# TLV521.net
KiCad netlist of a schematic drawn in Altium Designer
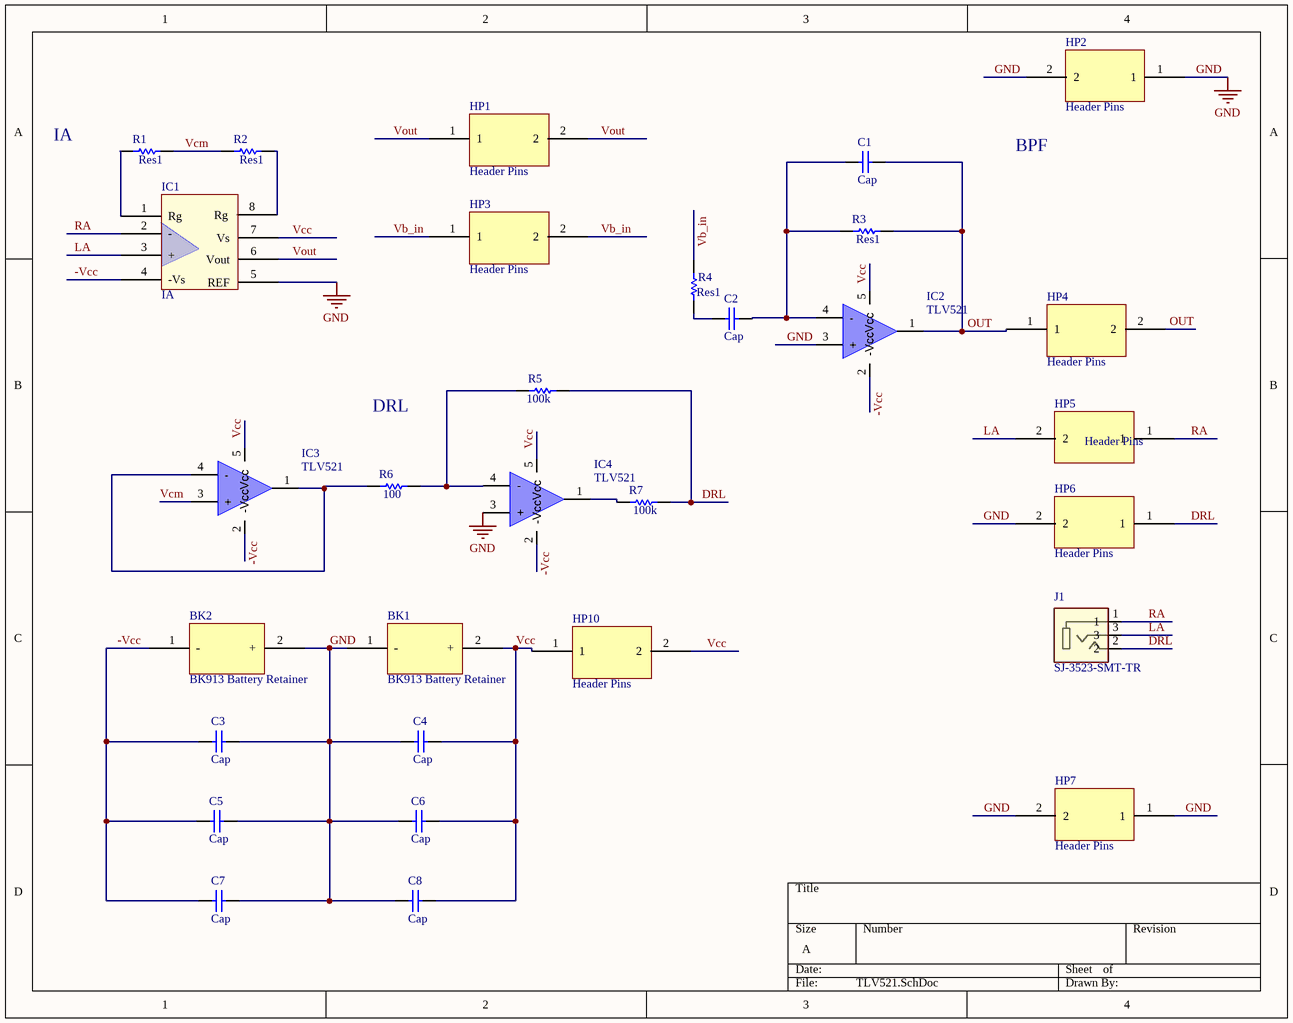
[diagram p0: TLV521.SchDoc]

(export (version "E")
  (design (tool "Eeschema 10.0.6"))
  (components
    (comp (ref "BK1")
      (value "BK913 Battery Retainer")
      (footprint "BK913")
      (description "BATTERY RETAINER COIN PC PIN")
      (libsource (lib "TLV521") (part "BK-913"))
    )
    (comp (ref "BK2")
      (value "BK913 Battery Retainer")
      (footprint "BK913")
      (description "BATTERY RETAINER COIN PC PIN")
      (libsource (lib "TLV521") (part "BK-913"))
    )
    (comp (ref "C1")
      (value "Cap")
      (footprint "6-0805_M")
      (description "Capacitor")
      (fields (field (name "PUBLISHER") "Altium Limited"))
      (libsource (lib "Miscellaneous Devices") (part "Cap"))
    )
    (comp (ref "C2")
      (value "Cap")
      (footprint "6-0805_M")
      (description "Capacitor")
      (fields (field (name "PUBLISHER") "Altium Limited"))
      (libsource (lib "Miscellaneous Devices") (part "Cap"))
    )
    (comp (ref "C3")
      (value "Cap")
      (footprint "6-0805_M")
      (description "Capacitor")
      (fields (field (name "PUBLISHER") "Altium Limited"))
      (libsource (lib "Miscellaneous Devices") (part "Cap"))
    )
    (comp (ref "C4")
      (value "Cap")
      (footprint "6-0805_M")
      (description "Capacitor")
      (fields (field (name "PUBLISHER") "Altium Limited"))
      (libsource (lib "Miscellaneous Devices") (part "Cap"))
    )
    (comp (ref "C5")
      (value "Cap")
      (footprint "6-0805_M")
      (description "Capacitor")
      (fields (field (name "PUBLISHER") "Altium Limited"))
      (libsource (lib "Miscellaneous Devices") (part "Cap"))
    )
    (comp (ref "C6")
      (value "Cap")
      (footprint "6-0805_M")
      (description "Capacitor")
      (fields (field (name "PUBLISHER") "Altium Limited"))
      (libsource (lib "Miscellaneous Devices") (part "Cap"))
    )
    (comp (ref "C7")
      (value "Cap")
      (footprint "6-0805_M")
      (description "Capacitor")
      (fields (field (name "PUBLISHER") "Altium Limited"))
      (libsource (lib "Miscellaneous Devices") (part "Cap"))
    )
    (comp (ref "C8")
      (value "Cap")
      (footprint "6-0805_M")
      (description "Capacitor")
      (fields (field (name "PUBLISHER") "Altium Limited"))
      (libsource (lib "Miscellaneous Devices") (part "Cap"))
    )
    (comp (ref "HP1")
      (value "Header Pins")
      (footprint "Header_Pins")
      (libsource (lib "") (part "Header Pins_1"))
    )
    (comp (ref "HP2")
      (value "Header Pins")
      (footprint "Header_Pins")
      (libsource (lib "TLV521") (part "Header Pins"))
    )
    (comp (ref "HP3")
      (value "Header Pins")
      (footprint "Header_Pins")
      (libsource (lib "") (part "Header Pins_1"))
    )
    (comp (ref "HP4")
      (value "Header Pins")
      (footprint "Header_Pins")
      (libsource (lib "") (part "Header Pins_1"))
    )
    (comp (ref "HP5")
      (value "Header Pins")
      (footprint "Header_Pins")
      (libsource (lib "TLV521") (part "Header Pins"))
    )
    (comp (ref "HP6")
      (value "Header Pins")
      (footprint "Header_Pins")
      (libsource (lib "TLV521") (part "Header Pins"))
    )
    (comp (ref "HP7")
      (value "Header Pins")
      (footprint "Header_Pins")
      (libsource (lib "TLV521") (part "Header Pins"))
    )
    (comp (ref "HP10")
      (value "Header Pins")
      (footprint "Header_Pins")
      (libsource (lib "") (part "Header Pins_1"))
    )
    (comp (ref "IC1")
      (value "IA")
      (footprint "SOP2")
      (description "IC OPAMP INSTR 1MHZ 8SOIC")
      (libsource (lib "TLV521") (part "AD620ARZ-REEL7"))
    )
    (comp (ref "IC2")
      (value "TLV521")
      (footprint "SOT65P210X110-5N")
      (description "IC OP AMP 6KHZ RR SC-70-5")
      (libsource (lib "TLV521") (part "TLV521DCKT"))
    )
    (comp (ref "IC3")
      (value "TLV521")
      (footprint "SOT65P210X110-5N")
      (description "IC OP AMP 6KHZ RR SC-70-5")
      (libsource (lib "TLV521") (part "TLV521DCKT"))
    )
    (comp (ref "IC4")
      (value "TLV521")
      (footprint "SOT65P210X110-5N")
      (description "IC OP AMP 6KHZ RR SC-70-5")
      (libsource (lib "TLV521") (part "TLV521DCKT"))
    )
    (comp (ref "J1")
      (value "SJ-3523-SMT-TR")
      (footprint "*CUI_SJ-3523-SMT-TR")
      (description "3.5 mm, Stereo, Right Angle, Surface Mount _SMT_, Audio Jack Connector")
      (fields (field (name "MF") "CUI Devices") (field (name "DIGI-KEY_PART_NUMBER") "CP-3523SJCT-ND"))
      (libsource (lib "TLV521") (part "SJ-3523-SMT-TR"))
    )
    (comp (ref "R1")
      (value "Res1")
      (footprint "6-0805_M")
      (description "Resistor")
      (fields (field (name "PUBLISHER") "Altium Limited"))
      (libsource (lib "Miscellaneous Devices") (part "Res1"))
    )
    (comp (ref "R2")
      (value "Res1")
      (footprint "6-0805_M")
      (description "Resistor")
      (fields (field (name "PUBLISHER") "Altium Limited"))
      (libsource (lib "Miscellaneous Devices") (part "Res1"))
    )
    (comp (ref "R3")
      (value "Res1")
      (footprint "6-0805_M")
      (description "Resistor")
      (fields (field (name "PUBLISHER") "Altium Limited"))
      (libsource (lib "Miscellaneous Devices") (part "Res1"))
    )
    (comp (ref "R4")
      (value "Res1")
      (footprint "6-0805_M")
      (description "Resistor")
      (fields (field (name "PUBLISHER") "Altium Limited"))
      (libsource (lib "Miscellaneous Devices") (part "Res1"))
    )
    (comp (ref "R5")
      (value "100k")
      (footprint "6-0805_M")
      (description "Resistor")
      (fields (field (name "PUBLISHER") "Altium Limited"))
      (libsource (lib "Miscellaneous Devices") (part "Res1"))
    )
    (comp (ref "R6")
      (value "100")
      (footprint "6-0805_M")
      (description "Resistor")
      (fields (field (name "PUBLISHER") "Altium Limited"))
      (libsource (lib "Miscellaneous Devices") (part "Res1"))
    )
    (comp (ref "R7")
      (value "100k")
      (footprint "6-0805_M")
      (description "Resistor")
      (fields (field (name "PUBLISHER") "Altium Limited"))
      (libsource (lib "Miscellaneous Devices") (part "Res1"))
    )
  )
  (nets
    (net (code "1") (name "/-Vcc") (class "Default")
      (node (ref "BK2") (pin "1") (pinfunction "-_1") (pintype "passive"))
      (node (ref "C3") (pin "1") (pinfunction "1_1") (pintype "passive"))
      (node (ref "C5") (pin "1") (pinfunction "1_1") (pintype "passive"))
      (node (ref "C7") (pin "1") (pinfunction "1_1") (pintype "passive"))
      (node (ref "IC1") (pin "4") (pinfunction "-Vs_4") (pintype "passive"))
      (node (ref "IC2") (pin "2") (pinfunction "-Vcc_2") (pintype "passive"))
      (node (ref "IC3") (pin "2") (pinfunction "-Vcc_2") (pintype "passive"))
      (node (ref "IC4") (pin "2") (pinfunction "-Vcc_2") (pintype "passive"))
    )
    (net (code "2") (name "/DRL") (class "Default")
      (node (ref "HP6") (pin "1") (pinfunction "1_1") (pintype "passive"))
      (node (ref "J1") (pin "2") (pinfunction "2_2") (pintype "passive"))
      (node (ref "R5") (pin "2") (pinfunction "2_2") (pintype "passive"))
      (node (ref "R7") (pin "2") (pinfunction "2_2") (pintype "passive"))
    )
    (net (code "3") (name "/LA") (class "Default")
      (node (ref "HP5") (pin "2") (pinfunction "2_2") (pintype "passive"))
      (node (ref "IC1") (pin "3") (pinfunction "+_3") (pintype "passive"))
      (node (ref "J1") (pin "3") (pinfunction "3_3") (pintype "passive"))
    )
    (net (code "4") (name "/OUT") (class "Default")
      (node (ref "C1") (pin "2") (pinfunction "2_2") (pintype "passive"))
      (node (ref "HP4") (pin "1") (pinfunction "1_1") (pintype "passive"))
      (node (ref "HP4") (pin "2") (pinfunction "2_2") (pintype "passive"))
      (node (ref "IC2") (pin "1") (pinfunction "Vout_1") (pintype "passive"))
      (node (ref "R3") (pin "2") (pinfunction "2_2") (pintype "passive"))
    )
    (net (code "5") (name "/RA") (class "Default")
      (node (ref "HP5") (pin "1") (pinfunction "1_1") (pintype "passive"))
      (node (ref "IC1") (pin "2") (pinfunction "-_2") (pintype "passive"))
      (node (ref "J1") (pin "1") (pinfunction "1_1") (pintype "passive"))
    )
    (net (code "6") (name "/Vb_in") (class "Default")
      (node (ref "HP3") (pin "1") (pinfunction "1_1") (pintype "passive"))
      (node (ref "HP3") (pin "2") (pinfunction "2_2") (pintype "passive"))
      (node (ref "R4") (pin "1") (pinfunction "1_1") (pintype "passive"))
    )
    (net (code "7") (name "/Vcc") (class "Default")
      (node (ref "BK1") (pin "2") (pinfunction "+_2") (pintype "passive"))
      (node (ref "C4") (pin "2") (pinfunction "2_2") (pintype "passive"))
      (node (ref "C6") (pin "2") (pinfunction "2_2") (pintype "passive"))
      (node (ref "C8") (pin "2") (pinfunction "2_2") (pintype "passive"))
      (node (ref "HP10") (pin "1") (pinfunction "1_1") (pintype "passive"))
      (node (ref "HP10") (pin "2") (pinfunction "2_2") (pintype "passive"))
      (node (ref "IC1") (pin "7") (pinfunction "Vs_7") (pintype "passive"))
      (node (ref "IC2") (pin "5") (pinfunction "Vcc_5") (pintype "passive"))
      (node (ref "IC3") (pin "5") (pinfunction "Vcc_5") (pintype "passive"))
      (node (ref "IC4") (pin "5") (pinfunction "Vcc_5") (pintype "passive"))
    )
    (net (code "8") (name "/Vcm") (class "Default")
      (node (ref "IC3") (pin "3") (pinfunction "+_3") (pintype "passive"))
      (node (ref "R1") (pin "2") (pinfunction "2_2") (pintype "passive"))
      (node (ref "R2") (pin "1") (pinfunction "1_1") (pintype "passive"))
    )
    (net (code "9") (name "/Vout") (class "Default")
      (node (ref "HP1") (pin "1") (pinfunction "1_1") (pintype "passive"))
      (node (ref "HP1") (pin "2") (pinfunction "2_2") (pintype "passive"))
      (node (ref "IC1") (pin "6") (pinfunction "Vout_6") (pintype "passive"))
    )
    (net (code "10") (name "GND") (class "Default")
      (node (ref "BK1") (pin "1") (pinfunction "-_1") (pintype "passive"))
      (node (ref "BK2") (pin "2") (pinfunction "+_2") (pintype "passive"))
      (node (ref "C3") (pin "2") (pinfunction "2_2") (pintype "passive"))
      (node (ref "C4") (pin "1") (pinfunction "1_1") (pintype "passive"))
      (node (ref "C5") (pin "2") (pinfunction "2_2") (pintype "passive"))
      (node (ref "C6") (pin "1") (pinfunction "1_1") (pintype "passive"))
      (node (ref "C7") (pin "2") (pinfunction "2_2") (pintype "passive"))
      (node (ref "C8") (pin "1") (pinfunction "1_1") (pintype "passive"))
      (node (ref "HP2") (pin "1") (pinfunction "1_1") (pintype "passive"))
      (node (ref "HP2") (pin "2") (pinfunction "2_2") (pintype "passive"))
      (node (ref "HP6") (pin "2") (pinfunction "2_2") (pintype "passive"))
      (node (ref "HP7") (pin "1") (pinfunction "1_1") (pintype "passive"))
      (node (ref "HP7") (pin "2") (pinfunction "2_2") (pintype "passive"))
      (node (ref "IC1") (pin "5") (pinfunction "REF_5") (pintype "passive"))
      (node (ref "IC2") (pin "3") (pinfunction "+_3") (pintype "passive"))
      (node (ref "IC4") (pin "3") (pinfunction "+_3") (pintype "passive"))
    )
    (net (code "11") (name "Net-(C2-Pad1)") (class "Default")
      (node (ref "C2") (pin "1") (pinfunction "1_1") (pintype "passive"))
      (node (ref "R4") (pin "2") (pinfunction "2_2") (pintype "passive"))
    )
    (net (code "12") (name "Net-(IC1-Rg-Pad1)") (class "Default")
      (node (ref "IC1") (pin "1") (pinfunction "Rg_1") (pintype "passive"))
      (node (ref "R1") (pin "1") (pinfunction "1_1") (pintype "passive"))
    )
    (net (code "13") (name "Net-(IC1-Rg-Pad8)") (class "Default")
      (node (ref "IC1") (pin "8") (pinfunction "Rg_8") (pintype "passive"))
      (node (ref "R2") (pin "2") (pinfunction "2_2") (pintype "passive"))
    )
    (net (code "14") (name "Net-(IC2--)") (class "Default")
      (node (ref "C1") (pin "1") (pinfunction "1_1") (pintype "passive"))
      (node (ref "C2") (pin "2") (pinfunction "2_2") (pintype "passive"))
      (node (ref "IC2") (pin "4") (pinfunction "-_4") (pintype "passive"))
      (node (ref "R3") (pin "1") (pinfunction "1_1") (pintype "passive"))
    )
    (net (code "15") (name "Net-(IC3--)") (class "Default")
      (node (ref "IC3") (pin "1") (pinfunction "Vout_1") (pintype "passive"))
      (node (ref "IC3") (pin "4") (pinfunction "-_4") (pintype "passive"))
      (node (ref "R6") (pin "1") (pinfunction "1_1") (pintype "passive"))
    )
    (net (code "16") (name "Net-(IC4--)") (class "Default")
      (node (ref "IC4") (pin "4") (pinfunction "-_4") (pintype "passive"))
      (node (ref "R5") (pin "1") (pinfunction "1_1") (pintype "passive"))
      (node (ref "R6") (pin "2") (pinfunction "2_2") (pintype "passive"))
    )
    (net (code "17") (name "Net-(IC4-Vout)") (class "Default")
      (node (ref "IC4") (pin "1") (pinfunction "Vout_1") (pintype "passive"))
      (node (ref "R7") (pin "1") (pinfunction "1_1") (pintype "passive"))
    )
  )
)
